# power_supplies.net
KiCad netlist of a schematic drawn in Altium Designer
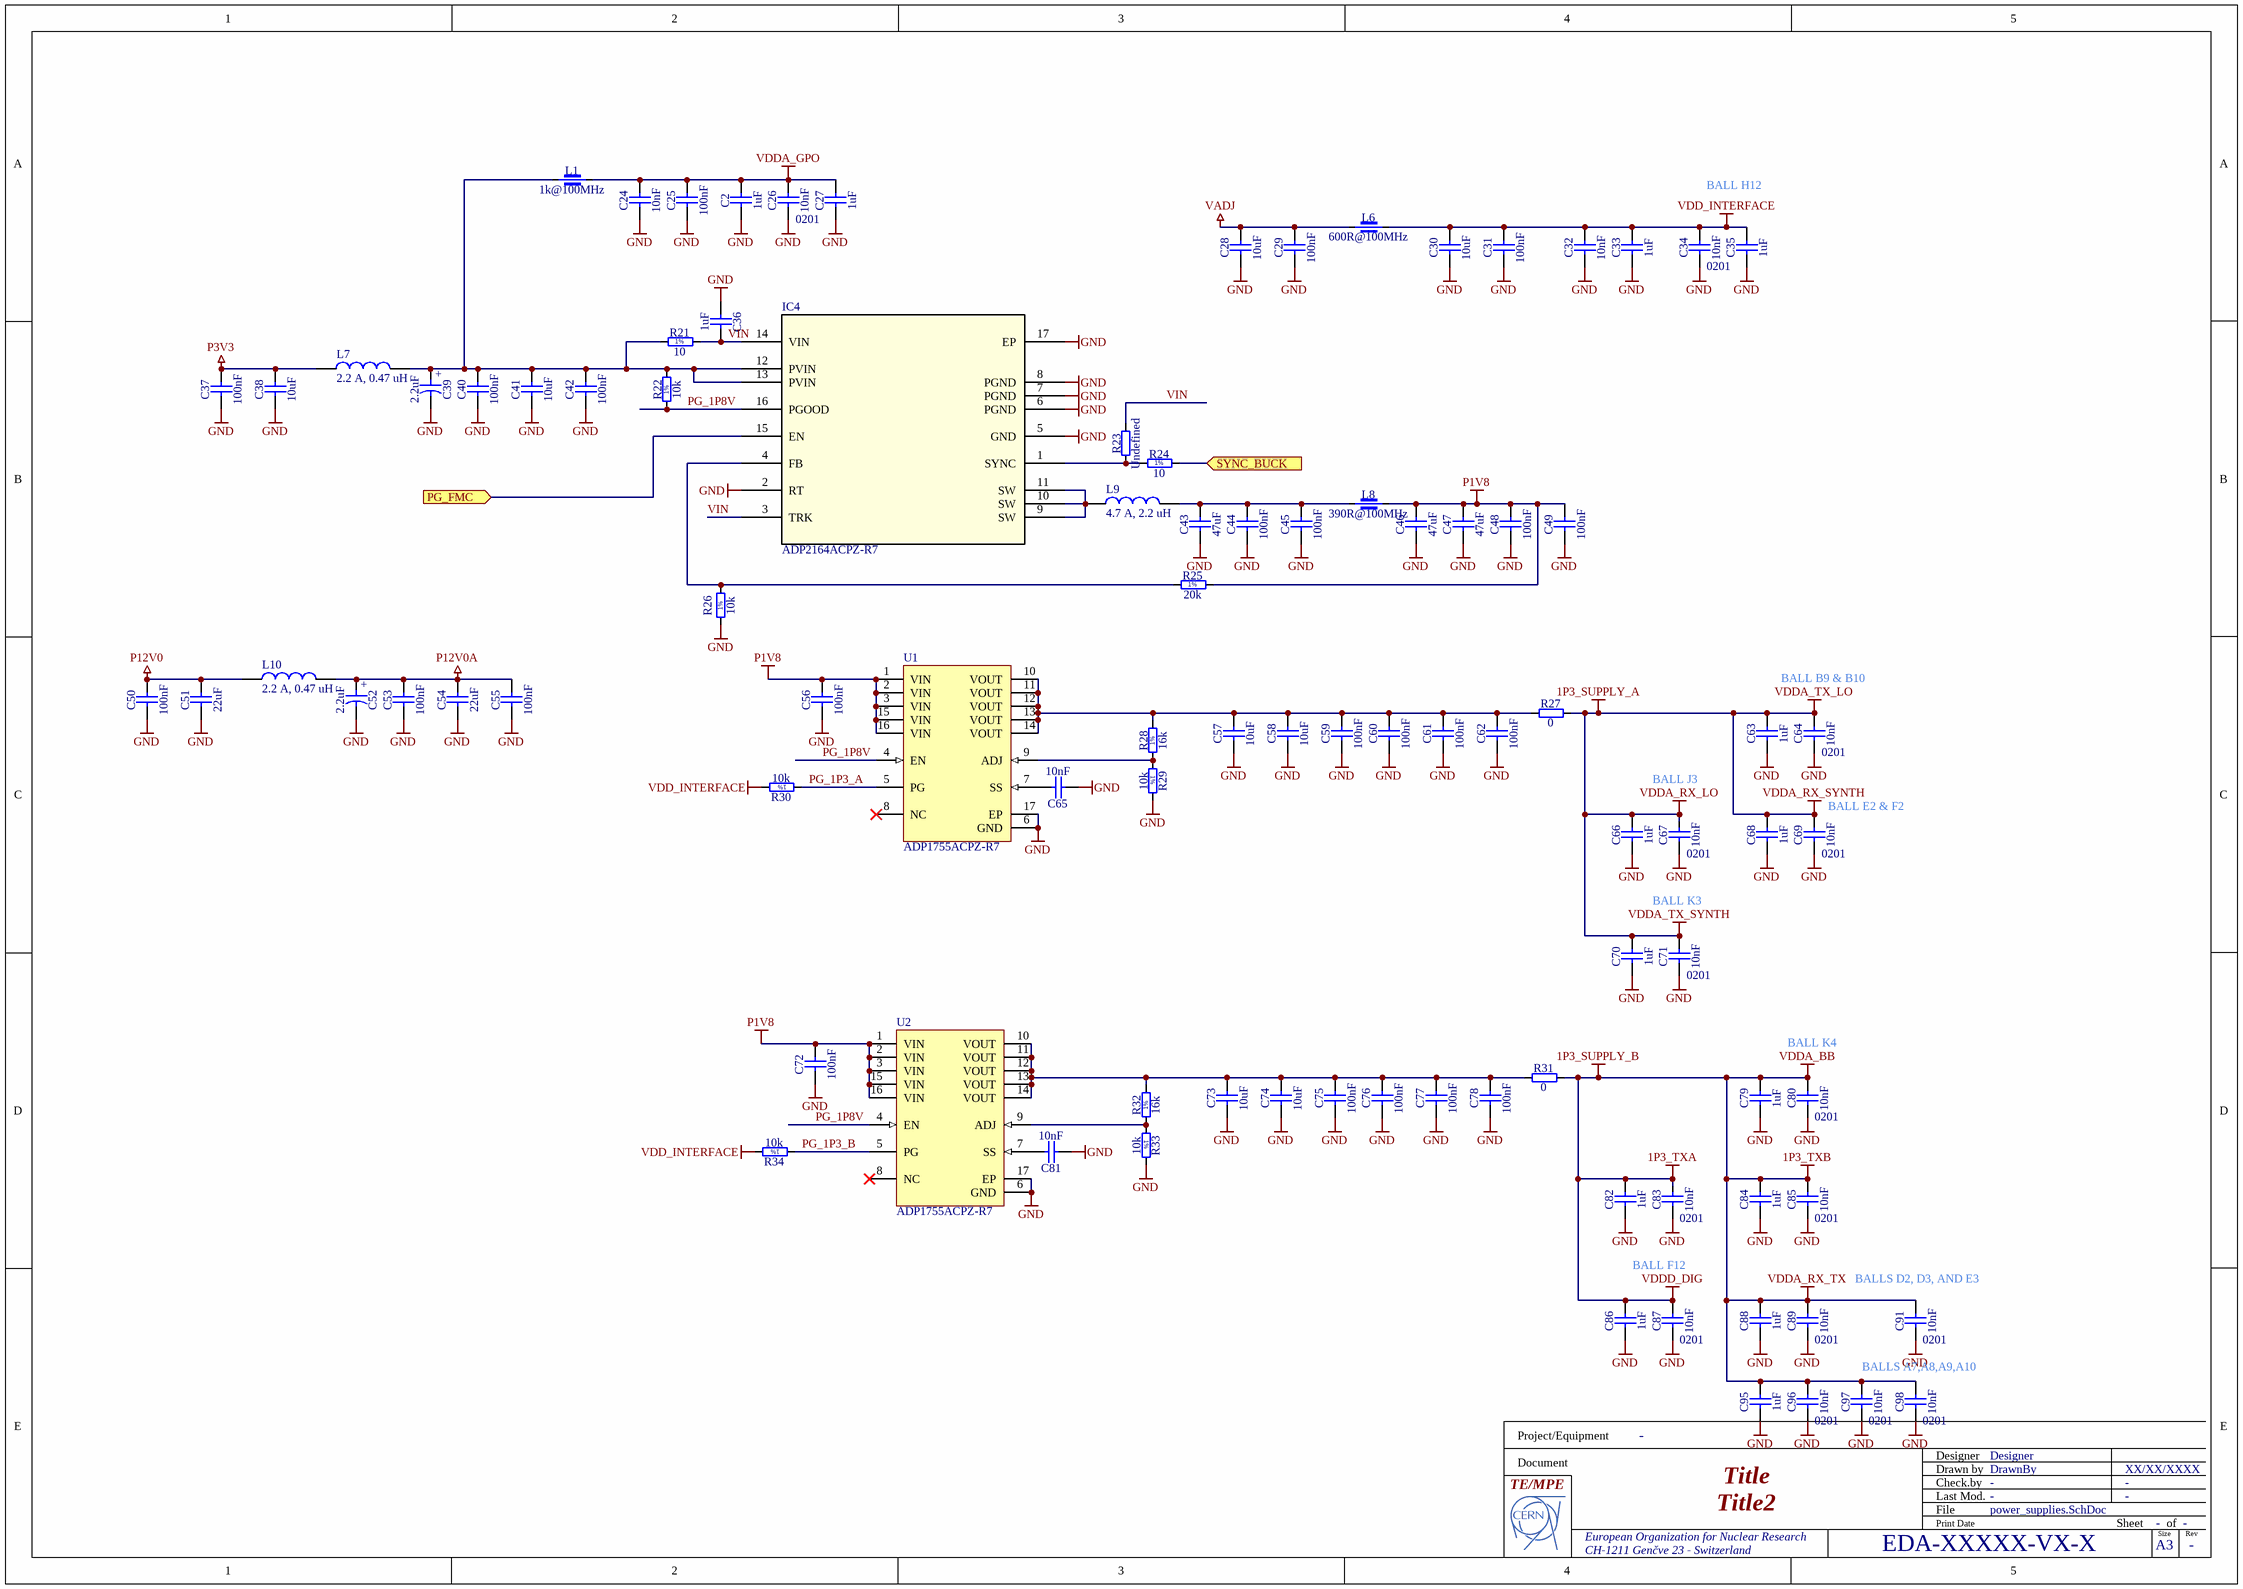
[diagram p0: power_supplies.SchDoc]

(export (version "E")
  (design (tool "Eeschema 10.0.6"))
  (components
    (comp (ref "C2")
      (value "1uF")
      (footprint "CAPC1005X55N")
      (description "Non-polarised capacitor")
      (fields
        (field (name "PART NUMBER") "CC0402_1UF_16V_10%_X5R")
        (field (name "VOLTAGE") "16V")
        (field (name "AUTHOR") "CERN DEM JLC")
      )
      (libsource (lib "Capacitors") (part "Capacitor - non polarized"))
    )
    (comp (ref "C24")
      (value "10nF")
      (footprint "CAPC1005X55N")
      (description "Non-polarised capacitor")
      (fields
        (field (name "PART NUMBER") "CC0402_10NF_16V_10%_X7R")
        (field (name "VOLTAGE") "16V")
        (field (name "AUTHOR") "CERN DEM JLC")
      )
      (libsource (lib "Capacitors") (part "Capacitor - non polarized"))
    )
    (comp (ref "C25")
      (value "100nF")
      (footprint "CAPC1005X55N")
      (description "Non-polarised capacitor")
      (fields
        (field (name "PART NUMBER") "CC0402_100NF_16V_10%_X7R")
        (field (name "VOLTAGE") "16V")
        (field (name "AUTHOR") "CERN DEM JLC")
      )
      (libsource (lib "Capacitors") (part "Capacitor - non polarized"))
    )
    (comp (ref "C26")
      (value "10nF")
      (footprint "CAPC0603X33N")
      (description "Non-polarised capacitor")
      (fields
        (field (name "PART NUMBER") "CC0201_10NF_10V_10%_X5R")
        (field (name "VOLTAGE") "10V")
        (field (name "CASE") "0201")
        (field (name "AUTHOR") "CERN DEM JLC")
      )
      (libsource (lib "Capacitors") (part "Capacitor - non polarized"))
    )
    (comp (ref "C27")
      (value "1uF")
      (footprint "CAPC1005X55N")
      (description "Non-polarised capacitor")
      (fields
        (field (name "PART NUMBER") "CC0402_1UF_16V_10%_X5R")
        (field (name "VOLTAGE") "16V")
        (field (name "AUTHOR") "CERN DEM JLC")
      )
      (libsource (lib "Capacitors") (part "Capacitor - non polarized"))
    )
    (comp (ref "C28")
      (value "10uF")
      (footprint "CAPC1608X87N")
      (description "Non-polarised capacitor")
      (fields
        (field (name "PART NUMBER") "CC0603_10UF_6.3V_20%_X5R")
        (field (name "VOLTAGE") "6.3V")
        (field (name "AUTHOR") "CERN DEM JLC")
      )
      (libsource (lib "Capacitors") (part "Capacitor - non polarized"))
    )
    (comp (ref "C29")
      (value "100nF")
      (footprint "CAPC1005X55N")
      (description "Non-polarised capacitor")
      (fields
        (field (name "PART NUMBER") "CC0402_100NF_16V_10%_X7R")
        (field (name "VOLTAGE") "16V")
        (field (name "AUTHOR") "CERN DEM JLC")
      )
      (libsource (lib "Capacitors") (part "Capacitor - non polarized"))
    )
    (comp (ref "C30")
      (value "10uF")
      (footprint "CAPC1608X87N")
      (description "Non-polarised capacitor")
      (fields
        (field (name "PART NUMBER") "CC0603_10UF_6.3V_20%_X5R")
        (field (name "VOLTAGE") "6.3V")
        (field (name "AUTHOR") "CERN DEM JLC")
      )
      (libsource (lib "Capacitors") (part "Capacitor - non polarized"))
    )
    (comp (ref "C31")
      (value "100nF")
      (footprint "CAPC1005X55N")
      (description "Non-polarised capacitor")
      (fields
        (field (name "PART NUMBER") "CC0402_100NF_16V_10%_X7R")
        (field (name "VOLTAGE") "16V")
        (field (name "AUTHOR") "CERN DEM JLC")
      )
      (libsource (lib "Capacitors") (part "Capacitor - non polarized"))
    )
    (comp (ref "C32")
      (value "10nF")
      (footprint "CAPC1005X55N")
      (description "Non-polarised capacitor")
      (fields
        (field (name "PART NUMBER") "CC0402_10NF_16V_10%_X7R")
        (field (name "VOLTAGE") "16V")
        (field (name "AUTHOR") "CERN DEM JLC")
      )
      (libsource (lib "Capacitors") (part "Capacitor - non polarized"))
    )
    (comp (ref "C33")
      (value "1uF")
      (footprint "CAPC1005X55N")
      (description "Non-polarised capacitor")
      (fields
        (field (name "PART NUMBER") "CC0402_1UF_16V_10%_X5R")
        (field (name "VOLTAGE") "16V")
        (field (name "AUTHOR") "CERN DEM JLC")
      )
      (libsource (lib "Capacitors") (part "Capacitor - non polarized"))
    )
    (comp (ref "C34")
      (value "10nF")
      (footprint "CAPC0603X33N")
      (description "Non-polarised capacitor")
      (fields
        (field (name "PART NUMBER") "CC0201_10NF_10V_10%_X5R")
        (field (name "VOLTAGE") "10V")
        (field (name "CASE") "0201")
        (field (name "AUTHOR") "CERN DEM JLC")
      )
      (libsource (lib "Capacitors") (part "Capacitor - non polarized"))
    )
    (comp (ref "C35")
      (value "1uF")
      (footprint "CAPC1005X55N")
      (description "Non-polarised capacitor")
      (fields
        (field (name "PART NUMBER") "CC0402_1UF_16V_10%_X5R")
        (field (name "VOLTAGE") "16V")
        (field (name "AUTHOR") "CERN DEM JLC")
      )
      (libsource (lib "Capacitors") (part "Capacitor - non polarized"))
    )
    (comp (ref "C36")
      (value "1uF")
      (footprint "CAPC1005X55N")
      (description "Non-polarised capacitor")
      (fields
        (field (name "PART NUMBER") "CC0402_1UF_16V_10%_X5R")
        (field (name "VOLTAGE") "16V")
        (field (name "AUTHOR") "CERN DEM JLC")
      )
      (libsource (lib "Capacitors") (part "Capacitor - non polarized"))
    )
    (comp (ref "C37")
      (value "100nF")
      (footprint "CAPC1005X55N")
      (description "Non-polarised capacitor")
      (fields
        (field (name "PART NUMBER") "CC0402_100NF_16V_10%_X7R")
        (field (name "VOLTAGE") "16V")
        (field (name "AUTHOR") "CERN DEM JLC")
      )
      (libsource (lib "Capacitors") (part "Capacitor - non polarized"))
    )
    (comp (ref "C38")
      (value "10uF")
      (footprint "CAPC1608X87N")
      (description "Non-polarised capacitor")
      (fields
        (field (name "PART NUMBER") "CC0603_10UF_6.3V_20%_X5R")
        (field (name "VOLTAGE") "6.3V")
        (field (name "AUTHOR") "CERN DEM JLC")
      )
      (libsource (lib "Capacitors") (part "Capacitor - non polarized"))
    )
    (comp (ref "C39")
      (value "2.2uF")
      (footprint "CAPMP3216X180N")
      (description "Polarised capacitor")
      (fields
        (field (name "PART NUMBER") "CTE3216-18_2.2UF_25V_10%")
        (field (name "VOLTAGE") "25V")
        (field (name "AUTHOR") "CERN DEM JLC")
      )
      (libsource (lib "Capacitors") (part "Capacitor - polarized"))
    )
    (comp (ref "C40")
      (value "100nF")
      (footprint "CAPC1005X55N")
      (description "Non-polarised capacitor")
      (fields
        (field (name "PART NUMBER") "CC0402_100NF_16V_10%_X7R")
        (field (name "VOLTAGE") "16V")
        (field (name "AUTHOR") "CERN DEM JLC")
      )
      (libsource (lib "Capacitors") (part "Capacitor - non polarized"))
    )
    (comp (ref "C41")
      (value "10uF")
      (footprint "CAPC1608X87N")
      (description "Non-polarised capacitor")
      (fields
        (field (name "PART NUMBER") "CC0603_10UF_6.3V_20%_X5R")
        (field (name "VOLTAGE") "6.3V")
        (field (name "AUTHOR") "CERN DEM JLC")
      )
      (libsource (lib "Capacitors") (part "Capacitor - non polarized"))
    )
    (comp (ref "C42")
      (value "100nF")
      (footprint "CAPC1005X55N")
      (description "Non-polarised capacitor")
      (fields
        (field (name "PART NUMBER") "CC0402_100NF_16V_10%_X7R")
        (field (name "VOLTAGE") "16V")
        (field (name "AUTHOR") "CERN DEM JLC")
      )
      (libsource (lib "Capacitors") (part "Capacitor - non polarized"))
    )
    (comp (ref "C43")
      (value "47uF")
      (footprint "CAPC3216X180N")
      (description "Non-polarised capacitor")
      (fields
        (field (name "PART NUMBER") "CC1206_47UF_25V_20%_X5R")
        (field (name "VOLTAGE") "25V")
        (field (name "AUTHOR") "CERN DEM JLC")
      )
      (libsource (lib "Capacitors") (part "Capacitor - non polarized"))
    )
    (comp (ref "C44")
      (value "100nF")
      (footprint "CAPC1005X55N")
      (description "Non-polarised capacitor")
      (fields
        (field (name "PART NUMBER") "CC0402_100NF_16V_10%_X7R")
        (field (name "VOLTAGE") "16V")
        (field (name "AUTHOR") "CERN DEM JLC")
      )
      (libsource (lib "Capacitors") (part "Capacitor - non polarized"))
    )
    (comp (ref "C45")
      (value "100nF")
      (footprint "CAPC1005X55N")
      (description "Non-polarised capacitor")
      (fields
        (field (name "PART NUMBER") "CC0402_100NF_16V_10%_X7R")
        (field (name "VOLTAGE") "16V")
        (field (name "AUTHOR") "CERN DEM JLC")
      )
      (libsource (lib "Capacitors") (part "Capacitor - non polarized"))
    )
    (comp (ref "C46")
      (value "47uF")
      (footprint "CAPC3216X180N")
      (description "Non-polarised capacitor")
      (fields
        (field (name "PART NUMBER") "CC1206_47UF_25V_20%_X5R")
        (field (name "VOLTAGE") "25V")
        (field (name "AUTHOR") "CERN DEM JLC")
      )
      (libsource (lib "Capacitors") (part "Capacitor - non polarized"))
    )
    (comp (ref "C47")
      (value "47uF")
      (footprint "CAPC3216X180N")
      (description "Non-polarised capacitor")
      (fields
        (field (name "PART NUMBER") "CC1206_47UF_25V_20%_X5R")
        (field (name "VOLTAGE") "25V")
        (field (name "AUTHOR") "CERN DEM JLC")
      )
      (libsource (lib "Capacitors") (part "Capacitor - non polarized"))
    )
    (comp (ref "C48")
      (value "100nF")
      (footprint "CAPC1005X55N")
      (description "Non-polarised capacitor")
      (fields
        (field (name "PART NUMBER") "CC0402_100NF_16V_10%_X7R")
        (field (name "VOLTAGE") "16V")
        (field (name "AUTHOR") "CERN DEM JLC")
      )
      (libsource (lib "Capacitors") (part "Capacitor - non polarized"))
    )
    (comp (ref "C49")
      (value "100nF")
      (footprint "CAPC1005X55N")
      (description "Non-polarised capacitor")
      (fields
        (field (name "PART NUMBER") "CC0402_100NF_16V_10%_X7R")
        (field (name "VOLTAGE") "16V")
        (field (name "AUTHOR") "CERN DEM JLC")
      )
      (libsource (lib "Capacitors") (part "Capacitor - non polarized"))
    )
    (comp (ref "C50")
      (value "100nF")
      (footprint "CAPC1005X55N")
      (description "Non-polarised capacitor")
      (fields
        (field (name "PART NUMBER") "CC0402_100NF_16V_10%_X7R")
        (field (name "VOLTAGE") "16V")
        (field (name "AUTHOR") "CERN DEM JLC")
      )
      (libsource (lib "Capacitors") (part "Capacitor - non polarized"))
    )
    (comp (ref "C51")
      (value "22uF")
      (footprint "CAPC3216X180N")
      (description "Non-polarised capacitor")
      (fields
        (field (name "PART NUMBER") "CC1206_22UF_35V_20%_JB_TDK_C3216JB1V226M160AC")
        (field (name "VOLTAGE") "35V")
        (field (name "AUTHOR") "CERN DEM JLC")
      )
      (libsource (lib "Capacitors") (part "Capacitor - non polarized"))
    )
    (comp (ref "C52")
      (value "2.2uF")
      (footprint "CAPMP3216X180N")
      (description "Polarised capacitor")
      (fields
        (field (name "PART NUMBER") "CTE3216-18_2.2UF_25V_10%")
        (field (name "VOLTAGE") "25V")
        (field (name "AUTHOR") "CERN DEM JLC")
      )
      (libsource (lib "Capacitors") (part "Capacitor - polarized"))
    )
    (comp (ref "C53")
      (value "100nF")
      (footprint "CAPC1005X55N")
      (description "Non-polarised capacitor")
      (fields
        (field (name "PART NUMBER") "CC0402_100NF_16V_10%_X7R")
        (field (name "VOLTAGE") "16V")
        (field (name "AUTHOR") "CERN DEM JLC")
      )
      (libsource (lib "Capacitors") (part "Capacitor - non polarized"))
    )
    (comp (ref "C54")
      (value "22uF")
      (footprint "CAPC3216X180N")
      (description "Non-polarised capacitor")
      (fields
        (field (name "PART NUMBER") "CC1206_22UF_35V_20%_JB_TDK_C3216JB1V226M160AC")
        (field (name "VOLTAGE") "35V")
        (field (name "AUTHOR") "CERN DEM JLC")
      )
      (libsource (lib "Capacitors") (part "Capacitor - non polarized"))
    )
    (comp (ref "C55")
      (value "100nF")
      (footprint "CAPC1005X55N")
      (description "Non-polarised capacitor")
      (fields
        (field (name "PART NUMBER") "CC0402_100NF_16V_10%_X7R")
        (field (name "VOLTAGE") "16V")
        (field (name "AUTHOR") "CERN DEM JLC")
      )
      (libsource (lib "Capacitors") (part "Capacitor - non polarized"))
    )
    (comp (ref "C56")
      (value "100nF")
      (footprint "CAPC1005X55N")
      (description "Non-polarised capacitor")
      (fields
        (field (name "PART NUMBER") "CC0402_100NF_16V_10%_X7R")
        (field (name "VOLTAGE") "16V")
        (field (name "AUTHOR") "CERN DEM JLC")
      )
      (libsource (lib "Capacitors") (part "Capacitor - non polarized"))
    )
    (comp (ref "C57")
      (value "10uF")
      (footprint "CAPC1608X87N")
      (description "Non-polarised capacitor")
      (fields
        (field (name "PART NUMBER") "CC0603_10UF_6.3V_20%_X5R")
        (field (name "VOLTAGE") "6.3V")
        (field (name "AUTHOR") "CERN DEM JLC")
      )
      (libsource (lib "Capacitors") (part "Capacitor - non polarized"))
    )
    (comp (ref "C58")
      (value "10uF")
      (footprint "CAPC1608X87N")
      (description "Non-polarised capacitor")
      (fields
        (field (name "PART NUMBER") "CC0603_10UF_6.3V_20%_X5R")
        (field (name "VOLTAGE") "6.3V")
        (field (name "AUTHOR") "CERN DEM JLC")
      )
      (libsource (lib "Capacitors") (part "Capacitor - non polarized"))
    )
    (comp (ref "C59")
      (value "100nF")
      (footprint "CAPC1005X55N")
      (description "Non-polarised capacitor")
      (fields
        (field (name "PART NUMBER") "CC0402_100NF_16V_10%_X7R")
        (field (name "VOLTAGE") "16V")
        (field (name "AUTHOR") "CERN DEM JLC")
      )
      (libsource (lib "Capacitors") (part "Capacitor - non polarized"))
    )
    (comp (ref "C60")
      (value "100nF")
      (footprint "CAPC1005X55N")
      (description "Non-polarised capacitor")
      (fields
        (field (name "PART NUMBER") "CC0402_100NF_16V_10%_X7R")
        (field (name "VOLTAGE") "16V")
        (field (name "AUTHOR") "CERN DEM JLC")
      )
      (libsource (lib "Capacitors") (part "Capacitor - non polarized"))
    )
    (comp (ref "C61")
      (value "100nF")
      (footprint "CAPC1005X55N")
      (description "Non-polarised capacitor")
      (fields
        (field (name "PART NUMBER") "CC0402_100NF_16V_10%_X7R")
        (field (name "VOLTAGE") "16V")
        (field (name "AUTHOR") "CERN DEM JLC")
      )
      (libsource (lib "Capacitors") (part "Capacitor - non polarized"))
    )
    (comp (ref "C62")
      (value "100nF")
      (footprint "CAPC1005X55N")
      (description "Non-polarised capacitor")
      (fields
        (field (name "PART NUMBER") "CC0402_100NF_16V_10%_X7R")
        (field (name "VOLTAGE") "16V")
        (field (name "AUTHOR") "CERN DEM JLC")
      )
      (libsource (lib "Capacitors") (part "Capacitor - non polarized"))
    )
    (comp (ref "C63")
      (value "1uF")
      (footprint "CAPC1005X55N")
      (description "Non-polarised capacitor")
      (fields
        (field (name "PART NUMBER") "CC0402_1UF_16V_10%_X5R")
        (field (name "VOLTAGE") "16V")
        (field (name "AUTHOR") "CERN DEM JLC")
      )
      (libsource (lib "Capacitors") (part "Capacitor - non polarized"))
    )
    (comp (ref "C64")
      (value "10nF")
      (footprint "CAPC0603X33N")
      (description "Non-polarised capacitor")
      (fields
        (field (name "PART NUMBER") "CC0201_10NF_10V_10%_X5R")
        (field (name "VOLTAGE") "10V")
        (field (name "CASE") "0201")
        (field (name "AUTHOR") "CERN DEM JLC")
      )
      (libsource (lib "Capacitors") (part "Capacitor - non polarized"))
    )
    (comp (ref "C65")
      (value "10nF")
      (footprint "CAPC1005X55N")
      (description "Non-polarised capacitor")
      (fields
        (field (name "PART NUMBER") "CC0402_10NF_16V_10%_X7R")
        (field (name "VOLTAGE") "16V")
        (field (name "AUTHOR") "CERN DEM JLC")
      )
      (libsource (lib "Capacitors") (part "Capacitor - non polarized"))
    )
    (comp (ref "C66")
      (value "1uF")
      (footprint "CAPC1005X55N")
      (description "Non-polarised capacitor")
      (fields
        (field (name "PART NUMBER") "CC0402_1UF_16V_10%_X5R")
        (field (name "VOLTAGE") "16V")
        (field (name "AUTHOR") "CERN DEM JLC")
      )
      (libsource (lib "Capacitors") (part "Capacitor - non polarized"))
    )
    (comp (ref "C67")
      (value "10nF")
      (footprint "CAPC0603X33N")
      (description "Non-polarised capacitor")
      (fields
        (field (name "PART NUMBER") "CC0201_10NF_10V_10%_X5R")
        (field (name "VOLTAGE") "10V")
        (field (name "CASE") "0201")
        (field (name "AUTHOR") "CERN DEM JLC")
      )
      (libsource (lib "Capacitors") (part "Capacitor - non polarized"))
    )
    (comp (ref "C68")
      (value "1uF")
      (footprint "CAPC1005X55N")
      (description "Non-polarised capacitor")
      (fields
        (field (name "PART NUMBER") "CC0402_1UF_16V_10%_X5R")
        (field (name "VOLTAGE") "16V")
        (field (name "AUTHOR") "CERN DEM JLC")
      )
      (libsource (lib "Capacitors") (part "Capacitor - non polarized"))
    )
    (comp (ref "C69")
      (value "10nF")
      (footprint "CAPC0603X33N")
      (description "Non-polarised capacitor")
      (fields
        (field (name "PART NUMBER") "CC0201_10NF_10V_10%_X5R")
        (field (name "VOLTAGE") "10V")
        (field (name "CASE") "0201")
        (field (name "AUTHOR") "CERN DEM JLC")
      )
      (libsource (lib "Capacitors") (part "Capacitor - non polarized"))
    )
    (comp (ref "C70")
      (value "1uF")
      (footprint "CAPC1005X55N")
      (description "Non-polarised capacitor")
      (fields
        (field (name "PART NUMBER") "CC0402_1UF_16V_10%_X5R")
        (field (name "VOLTAGE") "16V")
        (field (name "AUTHOR") "CERN DEM JLC")
      )
      (libsource (lib "Capacitors") (part "Capacitor - non polarized"))
    )
    (comp (ref "C71")
      (value "10nF")
      (footprint "CAPC0603X33N")
      (description "Non-polarised capacitor")
      (fields
        (field (name "PART NUMBER") "CC0201_10NF_10V_10%_X5R")
        (field (name "VOLTAGE") "10V")
        (field (name "CASE") "0201")
        (field (name "AUTHOR") "CERN DEM JLC")
      )
      (libsource (lib "Capacitors") (part "Capacitor - non polarized"))
    )
    (comp (ref "C72")
      (value "100nF")
      (footprint "CAPC1005X55N")
      (description "Non-polarised capacitor")
      (fields
        (field (name "PART NUMBER") "CC0402_100NF_16V_10%_X7R")
        (field (name "VOLTAGE") "16V")
        (field (name "AUTHOR") "CERN DEM JLC")
      )
      (libsource (lib "Capacitors") (part "Capacitor - non polarized"))
    )
    (comp (ref "C73")
      (value "10uF")
      (footprint "CAPC1608X87N")
      (description "Non-polarised capacitor")
      (fields
        (field (name "PART NUMBER") "CC0603_10UF_6.3V_20%_X5R")
        (field (name "VOLTAGE") "6.3V")
        (field (name "AUTHOR") "CERN DEM JLC")
      )
      (libsource (lib "Capacitors") (part "Capacitor - non polarized"))
    )
    (comp (ref "C74")
      (value "10uF")
      (footprint "CAPC1608X87N")
      (description "Non-polarised capacitor")
      (fields
        (field (name "PART NUMBER") "CC0603_10UF_6.3V_20%_X5R")
        (field (name "VOLTAGE") "6.3V")
        (field (name "AUTHOR") "CERN DEM JLC")
      )
      (libsource (lib "Capacitors") (part "Capacitor - non polarized"))
    )
    (comp (ref "C75")
      (value "100nF")
      (footprint "CAPC1005X55N")
      (description "Non-polarised capacitor")
      (fields
        (field (name "PART NUMBER") "CC0402_100NF_16V_10%_X7R")
        (field (name "VOLTAGE") "16V")
        (field (name "AUTHOR") "CERN DEM JLC")
      )
      (libsource (lib "Capacitors") (part "Capacitor - non polarized"))
    )
    (comp (ref "C76")
      (value "100nF")
      (footprint "CAPC1005X55N")
      (description "Non-polarised capacitor")
      (fields
        (field (name "PART NUMBER") "CC0402_100NF_16V_10%_X7R")
        (field (name "VOLTAGE") "16V")
        (field (name "AUTHOR") "CERN DEM JLC")
      )
      (libsource (lib "Capacitors") (part "Capacitor - non polarized"))
    )
    (comp (ref "C77")
      (value "100nF")
      (footprint "CAPC1005X55N")
      (description "Non-polarised capacitor")
      (fields
        (field (name "PART NUMBER") "CC0402_100NF_16V_10%_X7R")
        (field (name "VOLTAGE") "16V")
        (field (name "AUTHOR") "CERN DEM JLC")
      )
      (libsource (lib "Capacitors") (part "Capacitor - non polarized"))
    )
    (comp (ref "C78")
      (value "100nF")
      (footprint "CAPC1005X55N")
      (description "Non-polarised capacitor")
      (fields
        (field (name "PART NUMBER") "CC0402_100NF_16V_10%_X7R")
        (field (name "VOLTAGE") "16V")
        (field (name "AUTHOR") "CERN DEM JLC")
      )
      (libsource (lib "Capacitors") (part "Capacitor - non polarized"))
    )
    (comp (ref "C79")
      (value "1uF")
      (footprint "CAPC1005X55N")
      (description "Non-polarised capacitor")
      (fields
        (field (name "PART NUMBER") "CC0402_1UF_16V_10%_X5R")
        (field (name "VOLTAGE") "16V")
        (field (name "AUTHOR") "CERN DEM JLC")
      )
      (libsource (lib "Capacitors") (part "Capacitor - non polarized"))
    )
    (comp (ref "C80")
      (value "10nF")
      (footprint "CAPC0603X33N")
      (description "Non-polarised capacitor")
      (fields
        (field (name "PART NUMBER") "CC0201_10NF_10V_10%_X5R")
        (field (name "VOLTAGE") "10V")
        (field (name "CASE") "0201")
        (field (name "AUTHOR") "CERN DEM JLC")
      )
      (libsource (lib "Capacitors") (part "Capacitor - non polarized"))
    )
    (comp (ref "C81")
      (value "10nF")
      (footprint "CAPC1005X55N")
      (description "Non-polarised capacitor")
      (fields
        (field (name "PART NUMBER") "CC0402_10NF_16V_10%_X7R")
        (field (name "VOLTAGE") "16V")
        (field (name "AUTHOR") "CERN DEM JLC")
      )
      (libsource (lib "Capacitors") (part "Capacitor - non polarized"))
    )
    (comp (ref "C82")
      (value "1uF")
      (footprint "CAPC1005X55N")
      (description "Non-polarised capacitor")
      (fields
        (field (name "PART NUMBER") "CC0402_1UF_16V_10%_X5R")
        (field (name "VOLTAGE") "16V")
        (field (name "AUTHOR") "CERN DEM JLC")
      )
      (libsource (lib "Capacitors") (part "Capacitor - non polarized"))
    )
    (comp (ref "C83")
      (value "10nF")
      (footprint "CAPC0603X33N")
      (description "Non-polarised capacitor")
      (fields
        (field (name "PART NUMBER") "CC0201_10NF_10V_10%_X5R")
        (field (name "VOLTAGE") "10V")
        (field (name "CASE") "0201")
        (field (name "AUTHOR") "CERN DEM JLC")
      )
      (libsource (lib "Capacitors") (part "Capacitor - non polarized"))
    )
    (comp (ref "C84")
      (value "1uF")
      (footprint "CAPC1005X55N")
      (description "Non-polarised capacitor")
      (fields
        (field (name "PART NUMBER") "CC0402_1UF_16V_10%_X5R")
        (field (name "VOLTAGE") "16V")
        (field (name "AUTHOR") "CERN DEM JLC")
      )
      (libsource (lib "Capacitors") (part "Capacitor - non polarized"))
    )
    (comp (ref "C85")
      (value "10nF")
      (footprint "CAPC0603X33N")
      (description "Non-polarised capacitor")
      (fields
        (field (name "PART NUMBER") "CC0201_10NF_10V_10%_X5R")
        (field (name "VOLTAGE") "10V")
        (field (name "CASE") "0201")
        (field (name "AUTHOR") "CERN DEM JLC")
      )
      (libsource (lib "Capacitors") (part "Capacitor - non polarized"))
    )
    (comp (ref "C86")
      (value "1uF")
      (footprint "CAPC1005X55N")
      (description "Non-polarised capacitor")
      (fields
        (field (name "PART NUMBER") "CC0402_1UF_16V_10%_X5R")
        (field (name "VOLTAGE") "16V")
        (field (name "AUTHOR") "CERN DEM JLC")
      )
      (libsource (lib "Capacitors") (part "Capacitor - non polarized"))
    )
    (comp (ref "C87")
      (value "10nF")
      (footprint "CAPC0603X33N")
      (description "Non-polarised capacitor")
      (fields
        (field (name "PART NUMBER") "CC0201_10NF_10V_10%_X5R")
        (field (name "VOLTAGE") "10V")
        (field (name "CASE") "0201")
        (field (name "AUTHOR") "CERN DEM JLC")
      )
      (libsource (lib "Capacitors") (part "Capacitor - non polarized"))
    )
    (comp (ref "C88")
      (value "1uF")
      (footprint "CAPC1005X55N")
      (description "Non-polarised capacitor")
      (fields
        (field (name "PART NUMBER") "CC0402_1UF_16V_10%_X5R")
        (field (name "VOLTAGE") "16V")
        (field (name "AUTHOR") "CERN DEM JLC")
      )
      (libsource (lib "Capacitors") (part "Capacitor - non polarized"))
    )
    (comp (ref "C89")
      (value "10nF")
      (footprint "CAPC0603X33N")
      (description "Non-polarised capacitor")
      (fields
        (field (name "PART NUMBER") "CC0201_10NF_10V_10%_X5R")
        (field (name "VOLTAGE") "10V")
        (field (name "CASE") "0201")
        (field (name "AUTHOR") "CERN DEM JLC")
      )
      (libsource (lib "Capacitors") (part "Capacitor - non polarized"))
    )
    (comp (ref "C91")
      (value "10nF")
      (footprint "CAPC0603X33N")
      (description "Non-polarised capacitor")
      (fields
        (field (name "PART NUMBER") "CC0201_10NF_10V_10%_X5R")
        (field (name "VOLTAGE") "10V")
        (field (name "CASE") "0201")
        (field (name "AUTHOR") "CERN DEM JLC")
      )
      (libsource (lib "Capacitors") (part "Capacitor - non polarized"))
    )
    (comp (ref "C95")
      (value "1uF")
      (footprint "CAPC1005X55N")
      (description "Non-polarised capacitor")
      (fields
        (field (name "PART NUMBER") "CC0402_1UF_16V_10%_X5R")
        (field (name "VOLTAGE") "16V")
        (field (name "AUTHOR") "CERN DEM JLC")
      )
      (libsource (lib "Capacitors") (part "Capacitor - non polarized"))
    )
    (comp (ref "C96")
      (value "10nF")
      (footprint "CAPC0603X33N")
      (description "Non-polarised capacitor")
      (fields
        (field (name "PART NUMBER") "CC0201_10NF_10V_10%_X5R")
        (field (name "VOLTAGE") "10V")
        (field (name "CASE") "0201")
        (field (name "AUTHOR") "CERN DEM JLC")
      )
      (libsource (lib "Capacitors") (part "Capacitor - non polarized"))
    )
    (comp (ref "C97")
      (value "10nF")
      (footprint "CAPC0603X33N")
      (description "Non-polarised capacitor")
      (fields
        (field (name "PART NUMBER") "CC0201_10NF_10V_10%_X5R")
        (field (name "VOLTAGE") "10V")
        (field (name "CASE") "0201")
        (field (name "AUTHOR") "CERN DEM JLC")
      )
      (libsource (lib "Capacitors") (part "Capacitor - non polarized"))
    )
    (comp (ref "C98")
      (value "10nF")
      (footprint "CAPC0603X33N")
      (description "Non-polarised capacitor")
      (fields
        (field (name "PART NUMBER") "CC0201_10NF_10V_10%_X5R")
        (field (name "VOLTAGE") "10V")
        (field (name "CASE") "0201")
        (field (name "AUTHOR") "CERN DEM JLC")
      )
      (libsource (lib "Capacitors") (part "Capacitor - non polarized"))
    )
    (comp (ref "IC4")
      (value "ADP2164ACPZ-R7")
      (footprint "CP_16_26")
      (description "6.5 V, 4 A, High Efficiency,Step-Down,DC-to-DC Regulator")
      (fields (field (name "COPYRIGHT") "Copyright (C) 2018 Accelerated Designs. All rights reserved"))
      (libsource (lib "LIBRARY_SCH") (part "PM_ADP2164ACPZ-R7"))
    )
    (comp (ref "L1")
      (value "1k@100MHz")
      (footprint "INDC1005X55N")
      (fields
        (field (name "PART NUMBER") "IND0402_MURATA_BLM15HD102SN1")
        (field (name "POWER") "250mA")
        (field (name "TOLERANCE") "±25%")
        (field (name "AUTHOR") "CERN DEM JLC")
      )
      (libsource (lib "Inductors & Transformers") (part "Ferrite Bead"))
    )
    (comp (ref "L6")
      (value "600R@100MHz")
      (footprint "INDC1608X75N")
      (fields
        (field (name "PART NUMBER") "IND0603_TDK_MMZ1608B601CTAH0")
        (field (name "POWER") "500mA")
        (field (name "TOLERANCE") "±25%")
        (field (name "AUTHOR") "CERN DEM JMW")
      )
      (libsource (lib "Inductors & Transformers") (part "Ferrite Bead"))
    )
    (comp (ref "L7")
      (value "2.2 A, 0.47 uH")
      (footprint "WE-MAIA_2506")
      (description "WE-MAIA SMD Power Inductor, size 2506, 2.2 A, 0.47 uH")
      (fields (field (name "PART NUMBER") "784383210047") (field (name "PUBLISHER") "Wurth Elektronik"))
      (libsource (lib "ALTIUM-WE-MAIA-rev17b") (part "784383210047"))
    )
    (comp (ref "L8")
      (value "390R@100MHz")
      (footprint "INDC1608X95N")
      (fields
        (field (name "PART NUMBER") "IND0603_TDK_MPZ1608R391A")
        (field (name "POWER") "1.2A")
        (field (name "TOLERANCE") "±25%")
        (field (name "AUTHOR") "CERN DEM JLC")
      )
      (libsource (lib "Inductors & Transformers") (part "Ferrite Bead"))
    )
    (comp (ref "L9")
      (value "4.7 A, 2.2 uH")
      (footprint "WE-MAIA_4020")
      (description "WE-MAIA SMD Power Inductor, size 4020, 4.7 A, 2.2 uH")
      (fields (field (name "PART NUMBER") "78438356022") (field (name "PUBLISHER") "Wurth Elektronik"))
      (libsource (lib "ALTIUM-WE-MAIA-rev17b") (part "78438356022"))
    )
    (comp (ref "L10")
      (value "2.2 A, 0.47 uH")
      (footprint "WE-MAIA_2506")
      (description "WE-MAIA SMD Power Inductor, size 2506, 2.2 A, 0.47 uH")
      (fields (field (name "PART NUMBER") "784383210047") (field (name "PUBLISHER") "Wurth Elektronik"))
      (libsource (lib "ALTIUM-WE-MAIA-rev17b") (part "784383210047"))
    )
    (comp (ref "R21")
      (value "10")
      (footprint "RESC1608X55N")
      (description "Resistor - 1%")
      (fields
        (field (name "PART NUMBER") "R0603_10R_1%_0.1W_200PPM")
        (field (name "POWER") "0.1W")
        (field (name "AUTHOR") "CERN DEM JLC")
      )
      (libsource (lib "Resistors") (part "Resistor - 1%"))
    )
    (comp (ref "R22")
      (value "10k")
      (footprint "RESC1005X40N")
      (description "Resistor - 1%")
      (fields
        (field (name "PART NUMBER") "R0402_10K_1%_0.0625W_100PPM")
        (field (name "POWER") "0.0625W")
        (field (name "AUTHOR") "CERN DEM JLC")
      )
      (libsource (lib "Resistors") (part "Resistor - 1%"))
    )
    (comp (ref "R23")
      (value "Undefined")
      (footprint "RESC1608X55N")
      (description "Resistor")
      (fields (field (name "PART NUMBER") "R0603_NO-VALUE") (field (name "AUTHOR") "CERN DEM JLC"))
      (libsource (lib "Resistors") (part "Resistor"))
    )
    (comp (ref "R24")
      (value "10")
      (footprint "RESC1608X55N")
      (description "Resistor - 1%")
      (fields
        (field (name "PART NUMBER") "R0603_10R_1%_0.1W_200PPM")
        (field (name "POWER") "0.1W")
        (field (name "AUTHOR") "CERN DEM JLC")
      )
      (libsource (lib "Resistors") (part "Resistor - 1%"))
    )
    (comp (ref "R25")
      (value "20k")
      (footprint "RESC1005X40N")
      (description "Resistor - 1%")
      (fields
        (field (name "PART NUMBER") "R0402_20K_1%_0.0625W_100PPM")
        (field (name "POWER") "0.0625W")
        (field (name "AUTHOR") "CERN DEM JLC")
      )
      (libsource (lib "Resistors") (part "Resistor - 1%"))
    )
    (comp (ref "R26")
      (value "10k")
      (footprint "RESC1005X40N")
      (description "Resistor - 1%")
      (fields
        (field (name "PART NUMBER") "R0402_10K_1%_0.0625W_100PPM")
        (field (name "POWER") "0.0625W")
        (field (name "AUTHOR") "CERN DEM JLC")
      )
      (libsource (lib "Resistors") (part "Resistor - 1%"))
    )
    (comp (ref "R27")
      (value "0")
      (footprint "RESC1608X55N")
      (description "Resistor")
      (fields
        (field (name "PART NUMBER") "R0603_0R_JUMPER")
        (field (name "MANUFACTURER") "GENERIC")
        (field (name "AUTHOR") "CERN DEM JLC")
      )
      (libsource (lib "Resistors") (part "Resistor"))
    )
    (comp (ref "R28")
      (value "16k")
      (footprint "RESC1005X40N")
      (description "Resistor - 1%")
      (fields
        (field (name "PART NUMBER") "R0402_16K_1%_0.0625W_100PPM")
        (field (name "POWER") "0.0625W")
        (field (name "AUTHOR") "CERN DEM JLC")
      )
      (libsource (lib "Resistors") (part "Resistor - 1%"))
    )
    (comp (ref "R29")
      (value "10k")
      (footprint "RESC1005X40N")
      (description "Resistor - 1%")
      (fields
        (field (name "PART NUMBER") "R0402_10K_1%_0.0625W_100PPM")
        (field (name "POWER") "0.0625W")
        (field (name "AUTHOR") "CERN DEM JLC")
      )
      (libsource (lib "Resistors") (part "Resistor - 1%"))
    )
    (comp (ref "R30")
      (value "10k")
      (footprint "RESC1005X40N")
      (description "Resistor - 1%")
      (fields
        (field (name "PART NUMBER") "R0402_10K_1%_0.0625W_100PPM")
        (field (name "POWER") "0.0625W")
        (field (name "AUTHOR") "CERN DEM JLC")
      )
      (libsource (lib "Resistors") (part "Resistor - 1%"))
    )
    (comp (ref "R31")
      (value "0")
      (footprint "RESC1608X55N")
      (description "Resistor")
      (fields
        (field (name "PART NUMBER") "R0603_0R_JUMPER")
        (field (name "MANUFACTURER") "GENERIC")
        (field (name "AUTHOR") "CERN DEM JLC")
      )
      (libsource (lib "Resistors") (part "Resistor"))
    )
    (comp (ref "R32")
      (value "16k")
      (footprint "RESC1005X40N")
      (description "Resistor - 1%")
      (fields
        (field (name "PART NUMBER") "R0402_16K_1%_0.0625W_100PPM")
        (field (name "POWER") "0.0625W")
        (field (name "AUTHOR") "CERN DEM JLC")
      )
      (libsource (lib "Resistors") (part "Resistor - 1%"))
    )
    (comp (ref "R33")
      (value "10k")
      (footprint "RESC1005X40N")
      (description "Resistor - 1%")
      (fields
        (field (name "PART NUMBER") "R0402_10K_1%_0.0625W_100PPM")
        (field (name "POWER") "0.0625W")
        (field (name "AUTHOR") "CERN DEM JLC")
      )
      (libsource (lib "Resistors") (part "Resistor - 1%"))
    )
    (comp (ref "R34")
      (value "10k")
      (footprint "RESC1005X40N")
      (description "Resistor - 1%")
      (fields
        (field (name "PART NUMBER") "R0402_10K_1%_0.0625W_100PPM")
        (field (name "POWER") "0.0625W")
        (field (name "AUTHOR") "CERN DEM JLC")
      )
      (libsource (lib "Resistors") (part "Resistor - 1%"))
    )
    (comp (ref "U1")
      (value "ADP1755ACPZ-R7")
      (footprint "CP-16-4_L")
      (fields (field (name "MANUFACTURER") "Analog Devices"))
      (libsource (lib "Altium Content Vault") (part "ADI-ADP1755-CP-16-4"))
    )
    (comp (ref "U2")
      (value "ADP1755ACPZ-R7")
      (footprint "CP-16-4_L")
      (fields (field (name "MANUFACTURER") "Analog Devices"))
      (libsource (lib "Altium Content Vault") (part "ADI-ADP1755-CP-16-4"))
    )
  )
  (nets
    (net (code "1") (name "/PG_1P3_A") (class "Default")
      (node (ref "R30") (pin "1") (pinfunction "1_1") (pintype "passive"))
      (node (ref "U1") (pin "5") (pinfunction "PG_5") (pintype "open_collector"))
    )
    (net (code "2") (name "/PG_1P3_B") (class "Default")
      (node (ref "R34") (pin "1") (pinfunction "1_1") (pintype "passive"))
      (node (ref "U2") (pin "5") (pinfunction "PG_5") (pintype "open_collector"))
    )
    (net (code "3") (name "/PG_1P8V") (class "Default")
      (node (ref "IC4") (pin "16") (pinfunction "PGOOD_16") (pintype "passive"))
      (node (ref "R22") (pin "1") (pinfunction "1_1") (pintype "passive"))
      (node (ref "U1") (pin "4") (pinfunction "EN_4") (pintype "input"))
      (node (ref "U2") (pin "4") (pinfunction "EN_4") (pintype "input"))
    )
    (net (code "4") (name "/PG_FMC") (class "Default")
      (node (ref "IC4") (pin "15") (pinfunction "EN_15") (pintype "passive"))
    )
    (net (code "5") (name "/SYNC_BUCK") (class "Default")
      (node (ref "R24") (pin "2") (pinfunction "2_2") (pintype "passive"))
    )
    (net (code "6") (name "/VIN") (class "Default")
      (node (ref "C36") (pin "2") (pinfunction "2_2") (pintype "passive"))
      (node (ref "IC4") (pin "14") (pinfunction "VIN_14") (pintype "passive"))
      (node (ref "IC4") (pin "3") (pinfunction "TRK_3") (pintype "passive"))
      (node (ref "R21") (pin "2") (pinfunction "2_2") (pintype "passive"))
      (node (ref "R23") (pin "2") (pinfunction "2_2") (pintype "passive"))
    )
    (net (code "7") (name "1P3_SUPPLY_A") (class "Default")
      (node (ref "C63") (pin "2") (pinfunction "2_2") (pintype "passive"))
      (node (ref "C64") (pin "2") (pinfunction "2_2") (pintype "passive"))
      (node (ref "C66") (pin "2") (pinfunction "2_2") (pintype "passive"))
      (node (ref "C67") (pin "2") (pinfunction "2_2") (pintype "passive"))
      (node (ref "C68") (pin "2") (pinfunction "2_2") (pintype "passive"))
      (node (ref "C69") (pin "2") (pinfunction "2_2") (pintype "passive"))
      (node (ref "C70") (pin "2") (pinfunction "2_2") (pintype "passive"))
      (node (ref "C71") (pin "2") (pinfunction "2_2") (pintype "passive"))
      (node (ref "R27") (pin "2") (pinfunction "2_2") (pintype "passive"))
    )
    (net (code "8") (name "1P3_SUPPLY_B") (class "Default")
      (node (ref "C79") (pin "2") (pinfunction "2_2") (pintype "passive"))
      (node (ref "C80") (pin "2") (pinfunction "2_2") (pintype "passive"))
      (node (ref "C82") (pin "2") (pinfunction "2_2") (pintype "passive"))
      (node (ref "C83") (pin "2") (pinfunction "2_2") (pintype "passive"))
      (node (ref "C84") (pin "2") (pinfunction "2_2") (pintype "passive"))
      (node (ref "C85") (pin "2") (pinfunction "2_2") (pintype "passive"))
      (node (ref "C86") (pin "2") (pinfunction "2_2") (pintype "passive"))
      (node (ref "C87") (pin "2") (pinfunction "2_2") (pintype "passive"))
      (node (ref "C88") (pin "2") (pinfunction "2_2") (pintype "passive"))
      (node (ref "C89") (pin "2") (pinfunction "2_2") (pintype "passive"))
      (node (ref "C91") (pin "2") (pinfunction "2_2") (pintype "passive"))
      (node (ref "C95") (pin "2") (pinfunction "2_2") (pintype "passive"))
      (node (ref "C96") (pin "2") (pinfunction "2_2") (pintype "passive"))
      (node (ref "C97") (pin "2") (pinfunction "2_2") (pintype "passive"))
      (node (ref "C98") (pin "2") (pinfunction "2_2") (pintype "passive"))
      (node (ref "R31") (pin "2") (pinfunction "2_2") (pintype "passive"))
    )
    (net (code "9") (name "GND") (class "Default")
      (node (ref "C2") (pin "1") (pinfunction "1_1") (pintype "passive"))
      (node (ref "C24") (pin "1") (pinfunction "1_1") (pintype "passive"))
      (node (ref "C25") (pin "1") (pinfunction "1_1") (pintype "passive"))
      (node (ref "C26") (pin "1") (pinfunction "1_1") (pintype "passive"))
      (node (ref "C27") (pin "1") (pinfunction "1_1") (pintype "passive"))
      (node (ref "C28") (pin "1") (pinfunction "1_1") (pintype "passive"))
      (node (ref "C29") (pin "1") (pinfunction "1_1") (pintype "passive"))
      (node (ref "C30") (pin "1") (pinfunction "1_1") (pintype "passive"))
      (node (ref "C31") (pin "1") (pinfunction "1_1") (pintype "passive"))
      (node (ref "C32") (pin "1") (pinfunction "1_1") (pintype "passive"))
      (node (ref "C33") (pin "1") (pinfunction "1_1") (pintype "passive"))
      (node (ref "C34") (pin "1") (pinfunction "1_1") (pintype "passive"))
      (node (ref "C35") (pin "1") (pinfunction "1_1") (pintype "passive"))
      (node (ref "C36") (pin "1") (pinfunction "1_1") (pintype "passive"))
      (node (ref "C37") (pin "1") (pinfunction "1_1") (pintype "passive"))
      (node (ref "C38") (pin "1") (pinfunction "1_1") (pintype "passive"))
      (node (ref "C39") (pin "2") (pinfunction "2_2") (pintype "passive"))
      (node (ref "C40") (pin "1") (pinfunction "1_1") (pintype "passive"))
      (node (ref "C41") (pin "1") (pinfunction "1_1") (pintype "passive"))
      (node (ref "C42") (pin "1") (pinfunction "1_1") (pintype "passive"))
      (node (ref "C43") (pin "1") (pinfunction "1_1") (pintype "passive"))
      (node (ref "C44") (pin "1") (pinfunction "1_1") (pintype "passive"))
      (node (ref "C45") (pin "1") (pinfunction "1_1") (pintype "passive"))
      (node (ref "C46") (pin "1") (pinfunction "1_1") (pintype "passive"))
      (node (ref "C47") (pin "1") (pinfunction "1_1") (pintype "passive"))
      (node (ref "C48") (pin "1") (pinfunction "1_1") (pintype "passive"))
      (node (ref "C49") (pin "1") (pinfunction "1_1") (pintype "passive"))
      (node (ref "C50") (pin "1") (pinfunction "1_1") (pintype "passive"))
      (node (ref "C51") (pin "1") (pinfunction "1_1") (pintype "passive"))
      (node (ref "C52") (pin "2") (pinfunction "2_2") (pintype "passive"))
      (node (ref "C53") (pin "1") (pinfunction "1_1") (pintype "passive"))
      (node (ref "C54") (pin "1") (pinfunction "1_1") (pintype "passive"))
      (node (ref "C55") (pin "1") (pinfunction "1_1") (pintype "passive"))
      (node (ref "C56") (pin "1") (pinfunction "1_1") (pintype "passive"))
      (node (ref "C57") (pin "1") (pinfunction "1_1") (pintype "passive"))
      (node (ref "C58") (pin "1") (pinfunction "1_1") (pintype "passive"))
      (node (ref "C59") (pin "1") (pinfunction "1_1") (pintype "passive"))
      (node (ref "C60") (pin "1") (pinfunction "1_1") (pintype "passive"))
      (node (ref "C61") (pin "1") (pinfunction "1_1") (pintype "passive"))
      (node (ref "C62") (pin "1") (pinfunction "1_1") (pintype "passive"))
      (node (ref "C63") (pin "1") (pinfunction "1_1") (pintype "passive"))
      (node (ref "C64") (pin "1") (pinfunction "1_1") (pintype "passive"))
      (node (ref "C65") (pin "1") (pinfunction "1_1") (pintype "passive"))
      (node (ref "C66") (pin "1") (pinfunction "1_1") (pintype "passive"))
      (node (ref "C67") (pin "1") (pinfunction "1_1") (pintype "passive"))
      (node (ref "C68") (pin "1") (pinfunction "1_1") (pintype "passive"))
      (node (ref "C69") (pin "1") (pinfunction "1_1") (pintype "passive"))
      (node (ref "C70") (pin "1") (pinfunction "1_1") (pintype "passive"))
      (node (ref "C71") (pin "1") (pinfunction "1_1") (pintype "passive"))
      (node (ref "C72") (pin "1") (pinfunction "1_1") (pintype "passive"))
      (node (ref "C73") (pin "1") (pinfunction "1_1") (pintype "passive"))
      (node (ref "C74") (pin "1") (pinfunction "1_1") (pintype "passive"))
      (node (ref "C75") (pin "1") (pinfunction "1_1") (pintype "passive"))
      (node (ref "C76") (pin "1") (pinfunction "1_1") (pintype "passive"))
      (node (ref "C77") (pin "1") (pinfunction "1_1") (pintype "passive"))
      (node (ref "C78") (pin "1") (pinfunction "1_1") (pintype "passive"))
      (node (ref "C79") (pin "1") (pinfunction "1_1") (pintype "passive"))
      (node (ref "C80") (pin "1") (pinfunction "1_1") (pintype "passive"))
      (node (ref "C81") (pin "1") (pinfunction "1_1") (pintype "passive"))
      (node (ref "C82") (pin "1") (pinfunction "1_1") (pintype "passive"))
      (node (ref "C83") (pin "1") (pinfunction "1_1") (pintype "passive"))
      (node (ref "C84") (pin "1") (pinfunction "1_1") (pintype "passive"))
      (node (ref "C85") (pin "1") (pinfunction "1_1") (pintype "passive"))
      (node (ref "C86") (pin "1") (pinfunction "1_1") (pintype "passive"))
      (node (ref "C87") (pin "1") (pinfunction "1_1") (pintype "passive"))
      (node (ref "C88") (pin "1") (pinfunction "1_1") (pintype "passive"))
      (node (ref "C89") (pin "1") (pinfunction "1_1") (pintype "passive"))
      (node (ref "C91") (pin "1") (pinfunction "1_1") (pintype "passive"))
      (node (ref "C95") (pin "1") (pinfunction "1_1") (pintype "passive"))
      (node (ref "C96") (pin "1") (pinfunction "1_1") (pintype "passive"))
      (node (ref "C97") (pin "1") (pinfunction "1_1") (pintype "passive"))
      (node (ref "C98") (pin "1") (pinfunction "1_1") (pintype "passive"))
      (node (ref "IC4") (pin "17") (pinfunction "EP_17") (pintype "passive"))
      (node (ref "IC4") (pin "2") (pinfunction "RT_2") (pintype "passive"))
      (node (ref "IC4") (pin "5") (pinfunction "GND_5") (pintype "passive"))
      (node (ref "IC4") (pin "6") (pinfunction "PGND_6") (pintype "passive"))
      (node (ref "IC4") (pin "7") (pinfunction "PGND_7") (pintype "passive"))
      (node (ref "IC4") (pin "8") (pinfunction "PGND_8") (pintype "passive"))
      (node (ref "R26") (pin "1") (pinfunction "1_1") (pintype "passive"))
      (node (ref "R29") (pin "2") (pinfunction "2_2") (pintype "passive"))
      (node (ref "R33") (pin "2") (pinfunction "2_2") (pintype "passive"))
      (node (ref "U1") (pin "17") (pinfunction "EP_17") (pintype "power_in"))
      (node (ref "U1") (pin "6") (pinfunction "GND_6") (pintype "power_in"))
      (node (ref "U2") (pin "17") (pinfunction "EP_17") (pintype "power_in"))
      (node (ref "U2") (pin "6") (pinfunction "GND_6") (pintype "power_in"))
    )
    (net (code "10") (name "Net-(C39-Pad1)") (class "Default")
      (node (ref "C39") (pin "1") (pinfunction "1_1") (pintype "passive"))
      (node (ref "C40") (pin "2") (pinfunction "2_2") (pintype "passive"))
      (node (ref "C41") (pin "2") (pinfunction "2_2") (pintype "passive"))
      (node (ref "C42") (pin "2") (pinfunction "2_2") (pintype "passive"))
      (node (ref "IC4") (pin "12") (pinfunction "PVIN_12") (pintype "passive"))
      (node (ref "IC4") (pin "13") (pinfunction "PVIN_13") (pintype "passive"))
      (node (ref "L1") (pin "1") (pinfunction "1_1") (pintype "passive"))
      (node (ref "L7") (pin "2") (pinfunction "2_2") (pintype "passive"))
      (node (ref "R21") (pin "1") (pinfunction "1_1") (pintype "passive"))
      (node (ref "R22") (pin "2") (pinfunction "2_2") (pintype "passive"))
    )
    (net (code "11") (name "Net-(C43-Pad2)") (class "Default")
      (node (ref "C43") (pin "2") (pinfunction "2_2") (pintype "passive"))
      (node (ref "C44") (pin "2") (pinfunction "2_2") (pintype "passive"))
      (node (ref "C45") (pin "2") (pinfunction "2_2") (pintype "passive"))
      (node (ref "L8") (pin "1") (pinfunction "1_1") (pintype "passive"))
      (node (ref "L9") (pin "2") (pinfunction "2_2") (pintype "passive"))
    )
    (net (code "12") (name "Net-(C57-Pad2)") (class "Default")
      (node (ref "C57") (pin "2") (pinfunction "2_2") (pintype "passive"))
      (node (ref "C58") (pin "2") (pinfunction "2_2") (pintype "passive"))
      (node (ref "C59") (pin "2") (pinfunction "2_2") (pintype "passive"))
      (node (ref "C60") (pin "2") (pinfunction "2_2") (pintype "passive"))
      (node (ref "C61") (pin "2") (pinfunction "2_2") (pintype "passive"))
      (node (ref "C62") (pin "2") (pinfunction "2_2") (pintype "passive"))
      (node (ref "R27") (pin "1") (pinfunction "1_1") (pintype "passive"))
      (node (ref "R28") (pin "2") (pinfunction "2_2") (pintype "passive"))
      (node (ref "U1") (pin "10") (pinfunction "VOUT_10") (pintype "power_in"))
      (node (ref "U1") (pin "11") (pinfunction "VOUT_11") (pintype "power_in"))
      (node (ref "U1") (pin "12") (pinfunction "VOUT_12") (pintype "power_in"))
      (node (ref "U1") (pin "13") (pinfunction "VOUT_13") (pintype "power_in"))
      (node (ref "U1") (pin "14") (pinfunction "VOUT_14") (pintype "power_in"))
    )
    (net (code "13") (name "Net-(C73-Pad2)") (class "Default")
      (node (ref "C73") (pin "2") (pinfunction "2_2") (pintype "passive"))
      (node (ref "C74") (pin "2") (pinfunction "2_2") (pintype "passive"))
      (node (ref "C75") (pin "2") (pinfunction "2_2") (pintype "passive"))
      (node (ref "C76") (pin "2") (pinfunction "2_2") (pintype "passive"))
      (node (ref "C77") (pin "2") (pinfunction "2_2") (pintype "passive"))
      (node (ref "C78") (pin "2") (pinfunction "2_2") (pintype "passive"))
      (node (ref "R31") (pin "1") (pinfunction "1_1") (pintype "passive"))
      (node (ref "R32") (pin "2") (pinfunction "2_2") (pintype "passive"))
      (node (ref "U2") (pin "10") (pinfunction "VOUT_10") (pintype "power_in"))
      (node (ref "U2") (pin "11") (pinfunction "VOUT_11") (pintype "power_in"))
      (node (ref "U2") (pin "12") (pinfunction "VOUT_12") (pintype "power_in"))
      (node (ref "U2") (pin "13") (pinfunction "VOUT_13") (pintype "power_in"))
      (node (ref "U2") (pin "14") (pinfunction "VOUT_14") (pintype "power_in"))
    )
    (net (code "14") (name "Net-(IC4-FB)") (class "Default")
      (node (ref "IC4") (pin "4") (pinfunction "FB_4") (pintype "passive"))
      (node (ref "R25") (pin "1") (pinfunction "1_1") (pintype "passive"))
      (node (ref "R26") (pin "2") (pinfunction "2_2") (pintype "passive"))
    )
    (net (code "15") (name "Net-(IC4-SW-Pad10)") (class "Default")
      (node (ref "IC4") (pin "10") (pinfunction "SW_10") (pintype "passive"))
      (node (ref "IC4") (pin "11") (pinfunction "SW_11") (pintype "passive"))
      (node (ref "IC4") (pin "9") (pinfunction "SW_9") (pintype "passive"))
      (node (ref "L9") (pin "1") (pinfunction "1_1") (pintype "passive"))
    )
    (net (code "16") (name "Net-(IC4-SYNC)") (class "Default")
      (node (ref "IC4") (pin "1") (pinfunction "SYNC_1") (pintype "passive"))
      (node (ref "R23") (pin "1") (pinfunction "1_1") (pintype "passive"))
      (node (ref "R24") (pin "1") (pinfunction "1_1") (pintype "passive"))
    )
    (net (code "17") (name "Net-(U1-ADJ)") (class "Default")
      (node (ref "R28") (pin "1") (pinfunction "1_1") (pintype "passive"))
      (node (ref "R29") (pin "1") (pinfunction "1_1") (pintype "passive"))
      (node (ref "U1") (pin "9") (pinfunction "ADJ_9") (pintype "input"))
    )
    (net (code "18") (name "Net-(U1-SS)") (class "Default")
      (node (ref "C65") (pin "2") (pinfunction "2_2") (pintype "passive"))
      (node (ref "U1") (pin "7") (pinfunction "SS_7") (pintype "input"))
    )
    (net (code "19") (name "Net-(U2-ADJ)") (class "Default")
      (node (ref "R32") (pin "1") (pinfunction "1_1") (pintype "passive"))
      (node (ref "R33") (pin "1") (pinfunction "1_1") (pintype "passive"))
      (node (ref "U2") (pin "9") (pinfunction "ADJ_9") (pintype "input"))
    )
    (net (code "20") (name "Net-(U2-SS)") (class "Default")
      (node (ref "C81") (pin "2") (pinfunction "2_2") (pintype "passive"))
      (node (ref "U2") (pin "7") (pinfunction "SS_7") (pintype "input"))
    )
    (net (code "21") (name "P1V8") (class "Default")
      (node (ref "C46") (pin "2") (pinfunction "2_2") (pintype "passive"))
      (node (ref "C47") (pin "2") (pinfunction "2_2") (pintype "passive"))
      (node (ref "C48") (pin "2") (pinfunction "2_2") (pintype "passive"))
      (node (ref "C49") (pin "2") (pinfunction "2_2") (pintype "passive"))
      (node (ref "C56") (pin "2") (pinfunction "2_2") (pintype "passive"))
      (node (ref "C72") (pin "2") (pinfunction "2_2") (pintype "passive"))
      (node (ref "L8") (pin "2") (pinfunction "2_2") (pintype "passive"))
      (node (ref "R25") (pin "2") (pinfunction "2_2") (pintype "passive"))
      (node (ref "U1") (pin "1") (pinfunction "VIN_1") (pintype "power_in"))
      (node (ref "U1") (pin "15") (pinfunction "VIN_15") (pintype "power_in"))
      (node (ref "U1") (pin "16") (pinfunction "VIN_16") (pintype "power_in"))
      (node (ref "U1") (pin "2") (pinfunction "VIN_2") (pintype "power_in"))
      (node (ref "U1") (pin "3") (pinfunction "VIN_3") (pintype "power_in"))
      (node (ref "U2") (pin "1") (pinfunction "VIN_1") (pintype "power_in"))
      (node (ref "U2") (pin "15") (pinfunction "VIN_15") (pintype "power_in"))
      (node (ref "U2") (pin "16") (pinfunction "VIN_16") (pintype "power_in"))
      (node (ref "U2") (pin "2") (pinfunction "VIN_2") (pintype "power_in"))
      (node (ref "U2") (pin "3") (pinfunction "VIN_3") (pintype "power_in"))
    )
    (net (code "22") (name "P3V3") (class "Default")
      (node (ref "C37") (pin "2") (pinfunction "2_2") (pintype "passive"))
      (node (ref "C38") (pin "2") (pinfunction "2_2") (pintype "passive"))
      (node (ref "L7") (pin "1") (pinfunction "1_1") (pintype "passive"))
    )
    (net (code "23") (name "P12V0") (class "Default")
      (node (ref "C50") (pin "2") (pinfunction "2_2") (pintype "passive"))
      (node (ref "C51") (pin "2") (pinfunction "2_2") (pintype "passive"))
      (node (ref "L10") (pin "1") (pinfunction "1_1") (pintype "passive"))
    )
    (net (code "24") (name "P12V0A") (class "Default")
      (node (ref "C52") (pin "1") (pinfunction "1_1") (pintype "passive"))
      (node (ref "C53") (pin "2") (pinfunction "2_2") (pintype "passive"))
      (node (ref "C54") (pin "2") (pinfunction "2_2") (pintype "passive"))
      (node (ref "C55") (pin "2") (pinfunction "2_2") (pintype "passive"))
      (node (ref "L10") (pin "2") (pinfunction "2_2") (pintype "passive"))
    )
    (net (code "25") (name "VADJ") (class "Default")
      (node (ref "C28") (pin "2") (pinfunction "2_2") (pintype "passive"))
      (node (ref "C29") (pin "2") (pinfunction "2_2") (pintype "passive"))
      (node (ref "L6") (pin "1") (pinfunction "1_1") (pintype "passive"))
    )
    (net (code "26") (name "VDDA_GPO") (class "Default")
      (node (ref "C2") (pin "2") (pinfunction "2_2") (pintype "passive"))
      (node (ref "C24") (pin "2") (pinfunction "2_2") (pintype "passive"))
      (node (ref "C25") (pin "2") (pinfunction "2_2") (pintype "passive"))
      (node (ref "C26") (pin "2") (pinfunction "2_2") (pintype "passive"))
      (node (ref "C27") (pin "2") (pinfunction "2_2") (pintype "passive"))
      (node (ref "L1") (pin "2") (pinfunction "2_2") (pintype "passive"))
    )
    (net (code "27") (name "VDD_INTERFACE") (class "Default")
      (node (ref "C30") (pin "2") (pinfunction "2_2") (pintype "passive"))
      (node (ref "C31") (pin "2") (pinfunction "2_2") (pintype "passive"))
      (node (ref "C32") (pin "2") (pinfunction "2_2") (pintype "passive"))
      (node (ref "C33") (pin "2") (pinfunction "2_2") (pintype "passive"))
      (node (ref "C34") (pin "2") (pinfunction "2_2") (pintype "passive"))
      (node (ref "C35") (pin "2") (pinfunction "2_2") (pintype "passive"))
      (node (ref "L6") (pin "2") (pinfunction "2_2") (pintype "passive"))
      (node (ref "R30") (pin "2") (pinfunction "2_2") (pintype "passive"))
      (node (ref "R34") (pin "2") (pinfunction "2_2") (pintype "passive"))
    )
    (net (code "28") (name "unconnected-(U1-NC-Pad8)") (class "Default")
      (node (ref "U1") (pin "8") (pinfunction "NC_8") (pintype "passive+no_connect"))
    )
    (net (code "29") (name "unconnected-(U2-NC-Pad8)") (class "Default")
      (node (ref "U2") (pin "8") (pinfunction "NC_8") (pintype "passive+no_connect"))
    )
  )
)
